# pipower-usb-gndplane.net
KiCad netlist of a schematic drawn in EAGLE
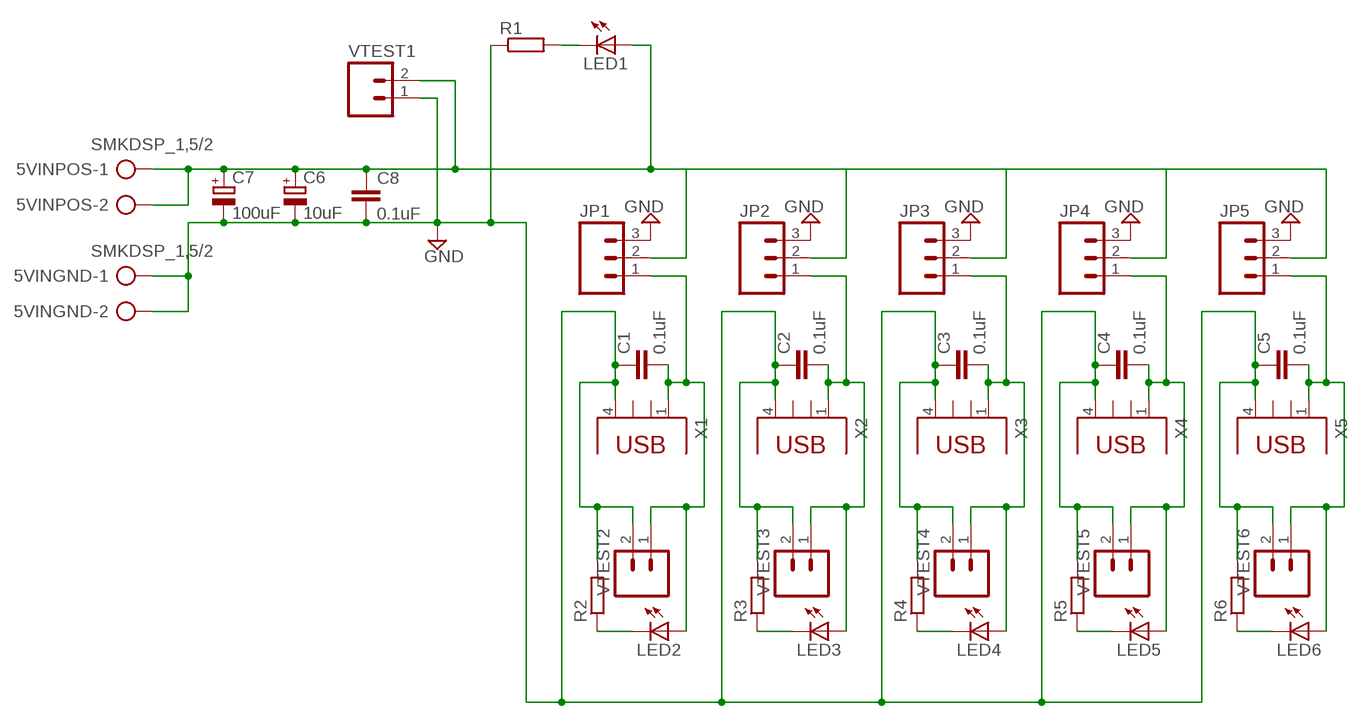
[diagram p0: schematic, sheet 1]

(export (version "E")
  (design (tool "Eeschema 10.0.6"))
  (components
    (comp (ref "5VINGND")
      (value "SMKDSP_1,5/2")
      (footprint "eagle-import:SMKDSP_1,5_2")
      (fields (field (name "MF") "FARNELL") (field (name "MPN") "1733570"))
      (libsource (lib "eagle-import") (part "SMKDSP_1,5/2"))
    )
    (comp (ref "5VINPOS")
      (value "SMKDSP_1,5/2")
      (footprint "eagle-import:SMKDSP_1,5_2")
      (fields (field (name "MF") "FARNELL") (field (name "MPN") "1733570"))
      (libsource (lib "eagle-import") (part "SMKDSP_1,5/2"))
    )
    (comp (ref "C1")
      (value "0.1uF")
      (footprint "eagle-import:CAP-PTH-5MM")
      (libsource (lib "eagle-import") (part "CAPPTH1"))
    )
    (comp (ref "C2")
      (value "0.1uF")
      (footprint "eagle-import:CAP-PTH-5MM")
      (libsource (lib "eagle-import") (part "CAPPTH1"))
    )
    (comp (ref "C3")
      (value "0.1uF")
      (footprint "eagle-import:CAP-PTH-5MM")
      (libsource (lib "eagle-import") (part "CAPPTH1"))
    )
    (comp (ref "C4")
      (value "0.1uF")
      (footprint "eagle-import:CAP-PTH-5MM")
      (libsource (lib "eagle-import") (part "CAPPTH1"))
    )
    (comp (ref "C5")
      (value "0.1uF")
      (footprint "eagle-import:CAP-PTH-5MM")
      (libsource (lib "eagle-import") (part "CAPPTH1"))
    )
    (comp (ref "C6")
      (value "10uF")
      (footprint "eagle-import:E5-10,5")
      (libsource (lib "eagle-import") (part "CPOL-EUE5-10.5"))
    )
    (comp (ref "C7")
      (value "100uF")
      (footprint "eagle-import:E5-10,5")
      (libsource (lib "eagle-import") (part "resistor_CPOL-EUE5-10.5"))
    )
    (comp (ref "C8")
      (value "0.1uF")
      (footprint "eagle-import:CAP-PTH-5MM")
      (libsource (lib "eagle-import") (part "CAPPTH1"))
    )
    (comp (ref "JP1")
      (value "M03LONGPADS")
      (footprint "eagle-import:1X03_LONGPADS")
      (libsource (lib "eagle-import") (part "M03LONGPADS"))
    )
    (comp (ref "JP2")
      (value "M03LONGPADS")
      (footprint "eagle-import:1X03_LONGPADS")
      (libsource (lib "eagle-import") (part "M03LONGPADS"))
    )
    (comp (ref "JP3")
      (value "M03LONGPADS")
      (footprint "eagle-import:1X03_LONGPADS")
      (libsource (lib "eagle-import") (part "M03LONGPADS"))
    )
    (comp (ref "JP4")
      (value "M03LONGPADS")
      (footprint "eagle-import:1X03_LONGPADS")
      (libsource (lib "eagle-import") (part "M03LONGPADS"))
    )
    (comp (ref "JP5")
      (value "M03LONGPADS")
      (footprint "eagle-import:1X03_LONGPADS")
      (libsource (lib "eagle-import") (part "M03LONGPADS"))
    )
    (comp (ref "LED1")
      (value "LED5MM")
      (footprint "eagle-import:LED5MM")
      (libsource (lib "eagle-import") (part "LED5MM"))
    )
    (comp (ref "LED2")
      (value "LED5MM")
      (footprint "eagle-import:LED5MM")
      (libsource (lib "eagle-import") (part "LED5MM"))
    )
    (comp (ref "LED3")
      (value "LED5MM")
      (footprint "eagle-import:LED5MM")
      (libsource (lib "eagle-import") (part "LED5MM"))
    )
    (comp (ref "LED4")
      (value "LED5MM")
      (footprint "eagle-import:LED5MM")
      (libsource (lib "eagle-import") (part "LED5MM"))
    )
    (comp (ref "LED5")
      (value "LED5MM")
      (footprint "eagle-import:LED5MM")
      (libsource (lib "eagle-import") (part "LED5MM"))
    )
    (comp (ref "LED6")
      (value "LED5MM")
      (footprint "eagle-import:LED5MM")
      (libsource (lib "eagle-import") (part "LED5MM"))
    )
    (comp (ref "R1")
      (value "R-EU_0207/12")
      (footprint "eagle-import:0207_12")
      (libsource (lib "eagle-import") (part "R-EU_0207/12"))
    )
    (comp (ref "R2")
      (value "R-EU_0207/12")
      (footprint "eagle-import:0207_12")
      (libsource (lib "eagle-import") (part "R-EU_0207/12"))
    )
    (comp (ref "R3")
      (value "R-EU_0207/12")
      (footprint "eagle-import:0207_12")
      (libsource (lib "eagle-import") (part "R-EU_0207/12"))
    )
    (comp (ref "R4")
      (value "R-EU_0207/12")
      (footprint "eagle-import:0207_12")
      (libsource (lib "eagle-import") (part "R-EU_0207/12"))
    )
    (comp (ref "R5")
      (value "R-EU_0207/12")
      (footprint "eagle-import:0207_12")
      (libsource (lib "eagle-import") (part "R-EU_0207/12"))
    )
    (comp (ref "R6")
      (value "R-EU_0207/12")
      (footprint "eagle-import:0207_12")
      (libsource (lib "eagle-import") (part "R-EU_0207/12"))
    )
    (comp (ref "VTEST1")
      (value "M02PTH3")
      (footprint "eagle-import:1X02_LONGPADS")
      (libsource (lib "eagle-import") (part "M02PTH3"))
    )
    (comp (ref "VTEST2")
      (value "M02PTH3")
      (footprint "eagle-import:1X02_LONGPADS")
      (libsource (lib "eagle-import") (part "M02PTH3"))
    )
    (comp (ref "VTEST3")
      (value "M02PTH3")
      (footprint "eagle-import:1X02_LONGPADS")
      (libsource (lib "eagle-import") (part "M02PTH3"))
    )
    (comp (ref "VTEST4")
      (value "M02PTH3")
      (footprint "eagle-import:1X02_LONGPADS")
      (libsource (lib "eagle-import") (part "M02PTH3"))
    )
    (comp (ref "VTEST5")
      (value "M02PTH3")
      (footprint "eagle-import:1X02_LONGPADS")
      (libsource (lib "eagle-import") (part "M02PTH3"))
    )
    (comp (ref "VTEST6")
      (value "M02PTH3")
      (footprint "eagle-import:1X02_LONGPADS")
      (libsource (lib "eagle-import") (part "M02PTH3"))
    )
    (comp (ref "X1")
      (value "PN87520")
      (footprint "eagle-import:PN87520")
      (libsource (lib "eagle-import") (part "PN87520"))
    )
    (comp (ref "X2")
      (value "PN87520")
      (footprint "eagle-import:PN87520")
      (libsource (lib "eagle-import") (part "PN87520"))
    )
    (comp (ref "X3")
      (value "PN87520")
      (footprint "eagle-import:PN87520")
      (libsource (lib "eagle-import") (part "PN87520"))
    )
    (comp (ref "X4")
      (value "PN87520")
      (footprint "eagle-import:PN87520")
      (libsource (lib "eagle-import") (part "PN87520"))
    )
    (comp (ref "X5")
      (value "PN87520")
      (footprint "eagle-import:PN87520")
      (libsource (lib "eagle-import") (part "PN87520"))
    )
  )
  (nets
    (net (code "1") (name "GND") (class "Default")
      (node (ref "5VINGND") (pin "1") (pinfunction "KL_1") (pintype "passive"))
      (node (ref "5VINGND") (pin "2") (pinfunction "KL_2") (pintype "passive"))
      (node (ref "C1") (pin "1") (pinfunction "1_1") (pintype "passive"))
      (node (ref "C2") (pin "1") (pinfunction "1_1") (pintype "passive"))
      (node (ref "C3") (pin "1") (pinfunction "1_1") (pintype "passive"))
      (node (ref "C4") (pin "1") (pinfunction "1_1") (pintype "passive"))
      (node (ref "C5") (pin "1") (pinfunction "1_1") (pintype "passive"))
      (node (ref "C6") (pin "-") (pinfunction "-_-") (pintype "passive"))
      (node (ref "C7") (pin "-") (pinfunction "-_-") (pintype "passive"))
      (node (ref "C8") (pin "2") (pinfunction "2_2") (pintype "passive"))
      (node (ref "JP1") (pin "3") (pinfunction "3_3") (pintype "passive"))
      (node (ref "JP2") (pin "3") (pinfunction "3_3") (pintype "passive"))
      (node (ref "JP3") (pin "3") (pinfunction "3_3") (pintype "passive"))
      (node (ref "JP4") (pin "3") (pinfunction "3_3") (pintype "passive"))
      (node (ref "JP5") (pin "3") (pinfunction "3_3") (pintype "passive"))
      (node (ref "R1") (pin "1") (pinfunction "1_1") (pintype "passive"))
      (node (ref "R2") (pin "2") (pinfunction "2_2") (pintype "passive"))
      (node (ref "R3") (pin "2") (pinfunction "2_2") (pintype "passive"))
      (node (ref "R4") (pin "2") (pinfunction "2_2") (pintype "passive"))
      (node (ref "R5") (pin "2") (pinfunction "2_2") (pintype "passive"))
      (node (ref "R6") (pin "2") (pinfunction "2_2") (pintype "passive"))
      (node (ref "VTEST1") (pin "1") (pinfunction "1_1") (pintype "passive"))
      (node (ref "VTEST2") (pin "2") (pinfunction "2_2") (pintype "passive"))
      (node (ref "VTEST3") (pin "2") (pinfunction "2_2") (pintype "passive"))
      (node (ref "VTEST4") (pin "2") (pinfunction "2_2") (pintype "passive"))
      (node (ref "VTEST5") (pin "2") (pinfunction "2_2") (pintype "passive"))
      (node (ref "VTEST6") (pin "2") (pinfunction "2_2") (pintype "passive"))
      (node (ref "X1") (pin "4") (pinfunction "4_4") (pintype "passive"))
      (node (ref "X2") (pin "4") (pinfunction "4_4") (pintype "passive"))
      (node (ref "X3") (pin "4") (pinfunction "4_4") (pintype "passive"))
      (node (ref "X4") (pin "4") (pinfunction "4_4") (pintype "passive"))
      (node (ref "X5") (pin "4") (pinfunction "4_4") (pintype "passive"))
    )
    (net (code "2") (name "Net-(5VINPOSA-KL)") (class "Default")
      (node (ref "5VINPOS") (pin "1") (pinfunction "KL_1") (pintype "passive"))
      (node (ref "5VINPOS") (pin "2") (pinfunction "KL_2") (pintype "passive"))
      (node (ref "C6") (pin "+") (pinfunction "+_+") (pintype "passive"))
      (node (ref "C7") (pin "+") (pinfunction "+_+") (pintype "passive"))
      (node (ref "C8") (pin "1") (pinfunction "1_1") (pintype "passive"))
      (node (ref "JP1") (pin "2") (pinfunction "2_2") (pintype "passive"))
      (node (ref "JP2") (pin "2") (pinfunction "2_2") (pintype "passive"))
      (node (ref "JP3") (pin "2") (pinfunction "2_2") (pintype "passive"))
      (node (ref "JP4") (pin "2") (pinfunction "2_2") (pintype "passive"))
      (node (ref "JP5") (pin "2") (pinfunction "2_2") (pintype "passive"))
      (node (ref "LED1") (pin "A") (pinfunction "A_A") (pintype "passive"))
      (node (ref "VTEST1") (pin "2") (pinfunction "2_2") (pintype "passive"))
    )
    (net (code "3") (name "Net-(C1-Pad2)") (class "Default")
      (node (ref "C1") (pin "2") (pinfunction "2_2") (pintype "passive"))
      (node (ref "JP1") (pin "1") (pinfunction "1_1") (pintype "passive"))
      (node (ref "LED2") (pin "A") (pinfunction "A_A") (pintype "passive"))
      (node (ref "VTEST2") (pin "1") (pinfunction "1_1") (pintype "passive"))
      (node (ref "X1") (pin "1") (pinfunction "1_1") (pintype "passive"))
    )
    (net (code "4") (name "Net-(C2-Pad2)") (class "Default")
      (node (ref "C2") (pin "2") (pinfunction "2_2") (pintype "passive"))
      (node (ref "JP2") (pin "1") (pinfunction "1_1") (pintype "passive"))
      (node (ref "LED3") (pin "A") (pinfunction "A_A") (pintype "passive"))
      (node (ref "VTEST3") (pin "1") (pinfunction "1_1") (pintype "passive"))
      (node (ref "X2") (pin "1") (pinfunction "1_1") (pintype "passive"))
    )
    (net (code "5") (name "Net-(C3-Pad2)") (class "Default")
      (node (ref "C3") (pin "2") (pinfunction "2_2") (pintype "passive"))
      (node (ref "JP3") (pin "1") (pinfunction "1_1") (pintype "passive"))
      (node (ref "LED4") (pin "A") (pinfunction "A_A") (pintype "passive"))
      (node (ref "VTEST4") (pin "1") (pinfunction "1_1") (pintype "passive"))
      (node (ref "X3") (pin "1") (pinfunction "1_1") (pintype "passive"))
    )
    (net (code "6") (name "Net-(C4-Pad2)") (class "Default")
      (node (ref "C4") (pin "2") (pinfunction "2_2") (pintype "passive"))
      (node (ref "JP4") (pin "1") (pinfunction "1_1") (pintype "passive"))
      (node (ref "LED5") (pin "A") (pinfunction "A_A") (pintype "passive"))
      (node (ref "VTEST5") (pin "1") (pinfunction "1_1") (pintype "passive"))
      (node (ref "X4") (pin "1") (pinfunction "1_1") (pintype "passive"))
    )
    (net (code "7") (name "Net-(C5-Pad2)") (class "Default")
      (node (ref "C5") (pin "2") (pinfunction "2_2") (pintype "passive"))
      (node (ref "JP5") (pin "1") (pinfunction "1_1") (pintype "passive"))
      (node (ref "LED6") (pin "A") (pinfunction "A_A") (pintype "passive"))
      (node (ref "VTEST6") (pin "1") (pinfunction "1_1") (pintype "passive"))
      (node (ref "X5") (pin "1") (pinfunction "1_1") (pintype "passive"))
    )
    (net (code "8") (name "Net-(LED1-C)") (class "Default")
      (node (ref "LED1") (pin "K") (pinfunction "C_K") (pintype "passive"))
      (node (ref "R1") (pin "2") (pinfunction "2_2") (pintype "passive"))
    )
    (net (code "9") (name "Net-(LED2-C)") (class "Default")
      (node (ref "LED2") (pin "K") (pinfunction "C_K") (pintype "passive"))
      (node (ref "R2") (pin "1") (pinfunction "1_1") (pintype "passive"))
    )
    (net (code "10") (name "Net-(LED3-C)") (class "Default")
      (node (ref "LED3") (pin "K") (pinfunction "C_K") (pintype "passive"))
      (node (ref "R3") (pin "1") (pinfunction "1_1") (pintype "passive"))
    )
    (net (code "11") (name "Net-(LED4-C)") (class "Default")
      (node (ref "LED4") (pin "K") (pinfunction "C_K") (pintype "passive"))
      (node (ref "R4") (pin "1") (pinfunction "1_1") (pintype "passive"))
    )
    (net (code "12") (name "Net-(LED5-C)") (class "Default")
      (node (ref "LED5") (pin "K") (pinfunction "C_K") (pintype "passive"))
      (node (ref "R5") (pin "1") (pinfunction "1_1") (pintype "passive"))
    )
    (net (code "13") (name "Net-(LED6-C)") (class "Default")
      (node (ref "LED6") (pin "K") (pinfunction "C_K") (pintype "passive"))
      (node (ref "R6") (pin "1") (pinfunction "1_1") (pintype "passive"))
    )
    (net (code "14") (name "unconnected-(X1-Pad2)") (class "Default")
      (node (ref "X1") (pin "2") (pinfunction "2_2") (pintype "passive"))
    )
    (net (code "15") (name "unconnected-(X1-Pad3)") (class "Default")
      (node (ref "X1") (pin "3") (pinfunction "3_3") (pintype "passive"))
    )
    (net (code "16") (name "unconnected-(X2-Pad2)") (class "Default")
      (node (ref "X2") (pin "2") (pinfunction "2_2") (pintype "passive"))
    )
    (net (code "17") (name "unconnected-(X2-Pad3)") (class "Default")
      (node (ref "X2") (pin "3") (pinfunction "3_3") (pintype "passive"))
    )
    (net (code "18") (name "unconnected-(X3-Pad2)") (class "Default")
      (node (ref "X3") (pin "2") (pinfunction "2_2") (pintype "passive"))
    )
    (net (code "19") (name "unconnected-(X3-Pad3)") (class "Default")
      (node (ref "X3") (pin "3") (pinfunction "3_3") (pintype "passive"))
    )
    (net (code "20") (name "unconnected-(X4-Pad2)") (class "Default")
      (node (ref "X4") (pin "2") (pinfunction "2_2") (pintype "passive"))
    )
    (net (code "21") (name "unconnected-(X4-Pad3)") (class "Default")
      (node (ref "X4") (pin "3") (pinfunction "3_3") (pintype "passive"))
    )
    (net (code "22") (name "unconnected-(X5-Pad2)") (class "Default")
      (node (ref "X5") (pin "2") (pinfunction "2_2") (pintype "passive"))
    )
    (net (code "23") (name "unconnected-(X5-Pad3)") (class "Default")
      (node (ref "X5") (pin "3") (pinfunction "3_3") (pintype "passive"))
    )
  )
)
